# Logica_ADC.net
KiCad netlist of a schematic drawn in Altium Designer
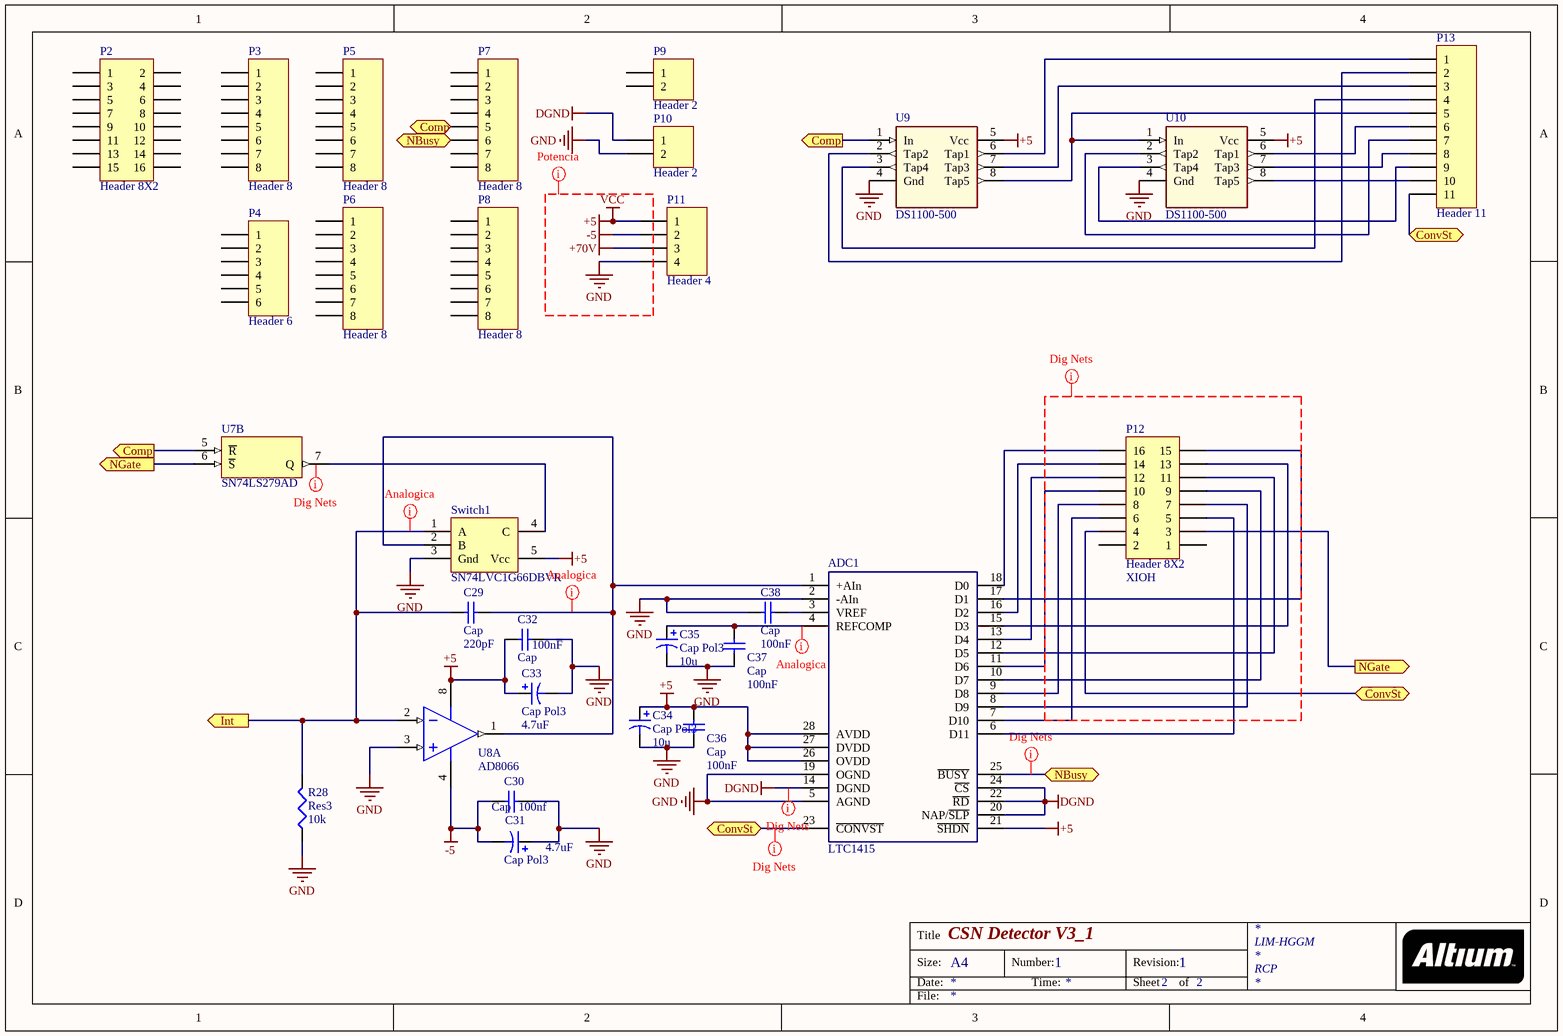
[diagram p0: Logica_ADC.SchDoc]

(export (version "E")
  (design (tool "Eeschema 10.0.6"))
  (components
    (comp (ref "ADC1")
      (value "LTC1415")
      (footprint "SO28_N")
      (libsource (lib "Integrated_Library1") (part "LTC1415"))
    )
    (comp (ref "C29")
      (value "Cap")
      (footprint "6-0805_N")
      (description "Capacitor")
      (fields (field (name "ALTIUM_VALUE") "220pF") (field (name "PUBLISHER") "Altium Limited"))
      (libsource (lib "Miscellaneous Devices") (part "Cap"))
    )
    (comp (ref "C30")
      (value "Cap")
      (footprint "6-0805_N")
      (description "Capacitor")
      (fields (field (name "ALTIUM_VALUE") "100nf") (field (name "PUBLISHER") "Altium Limited"))
      (libsource (lib "Miscellaneous Devices") (part "Cap"))
    )
    (comp (ref "C31")
      (value "Cap Pol3")
      (footprint "6-0805_N")
      (description "Polarized Capacitor (Surface Mount)")
      (fields (field (name "ALTIUM_VALUE") "4.7uF") (field (name "PUBLISHER") "Altium Limited"))
      (libsource (lib "Miscellaneous Devices") (part "Cap Pol3"))
    )
    (comp (ref "C32")
      (value "Cap")
      (footprint "6-0805_N")
      (description "Capacitor")
      (fields (field (name "ALTIUM_VALUE") "100nF") (field (name "PUBLISHER") "Altium Limited"))
      (libsource (lib "Miscellaneous Devices") (part "Cap"))
    )
    (comp (ref "C33")
      (value "Cap Pol3")
      (footprint "6-0805_N")
      (description "Polarized Capacitor (Surface Mount)")
      (fields (field (name "ALTIUM_VALUE") "4.7uF") (field (name "PUBLISHER") "Altium Limited"))
      (libsource (lib "Miscellaneous Devices") (part "Cap Pol3"))
    )
    (comp (ref "C34")
      (value "Cap Pol3")
      (footprint "6-0805_N")
      (description "Polarized Capacitor (Surface Mount)")
      (fields (field (name "ALTIUM_VALUE") "10u") (field (name "PUBLISHER") "Altium Limited"))
      (libsource (lib "Miscellaneous Devices") (part "Cap Pol3"))
    )
    (comp (ref "C35")
      (value "Cap Pol3")
      (footprint "6-0805_N")
      (description "Polarized Capacitor (Surface Mount)")
      (fields (field (name "ALTIUM_VALUE") "10u") (field (name "PUBLISHER") "Altium Limited"))
      (libsource (lib "Miscellaneous Devices") (part "Cap Pol3"))
    )
    (comp (ref "C36")
      (value "Cap")
      (footprint "6-0805_N")
      (description "Capacitor")
      (fields (field (name "ALTIUM_VALUE") "100nF") (field (name "PUBLISHER") "Altium Limited"))
      (libsource (lib "Miscellaneous Devices") (part "Cap"))
    )
    (comp (ref "C37")
      (value "Cap")
      (footprint "6-0805_N")
      (description "Capacitor")
      (fields (field (name "ALTIUM_VALUE") "100nF") (field (name "PUBLISHER") "Altium Limited"))
      (libsource (lib "Miscellaneous Devices") (part "Cap"))
    )
    (comp (ref "C38")
      (value "Cap")
      (footprint "6-0805_N")
      (description "Capacitor")
      (fields (field (name "ALTIUM_VALUE") "100nF") (field (name "PUBLISHER") "Altium Limited"))
      (libsource (lib "Miscellaneous Devices") (part "Cap"))
    )
    (comp (ref "P2")
      (value "Header 8X2")
      (footprint "HDR2X8")
      (description "Header, 8-Pin, Dual row")
      (fields (field (name "PUBLISHER") "Altium Limited"))
      (libsource (lib "Miscellaneous Connectors") (part "Header 8X2"))
    )
    (comp (ref "P3")
      (value "Header 8")
      (footprint "HDR1X8")
      (description "Header, 8-Pin")
      (fields (field (name "PUBLISHER") "Altium Limited"))
      (libsource (lib "Miscellaneous Connectors") (part "Header 8"))
    )
    (comp (ref "P4")
      (value "Header 6")
      (footprint "HDR1X6")
      (description "Header, 6-Pin")
      (fields (field (name "PUBLISHER") "Altium Limited"))
      (libsource (lib "Miscellaneous Connectors") (part "Header 6"))
    )
    (comp (ref "P5")
      (value "Header 8")
      (footprint "HDR1X8")
      (description "Header, 8-Pin")
      (fields (field (name "PUBLISHER") "Altium Limited"))
      (libsource (lib "Miscellaneous Connectors") (part "Header 8"))
    )
    (comp (ref "P6")
      (value "Header 8")
      (footprint "HDR1X8")
      (description "Header, 8-Pin")
      (fields (field (name "PUBLISHER") "Altium Limited"))
      (libsource (lib "Miscellaneous Connectors") (part "Header 8"))
    )
    (comp (ref "P7")
      (value "Header 8")
      (footprint "HDR1X8")
      (description "Header, 8-Pin")
      (fields (field (name "PUBLISHER") "Altium Limited"))
      (libsource (lib "Miscellaneous Connectors") (part "Header 8"))
    )
    (comp (ref "P8")
      (value "Header 8")
      (footprint "HDR1X8")
      (description "Header, 8-Pin")
      (fields (field (name "PUBLISHER") "Altium Limited"))
      (libsource (lib "Miscellaneous Connectors") (part "Header 8"))
    )
    (comp (ref "P9")
      (value "Header 2")
      (footprint "HDR1X2")
      (description "Header, 2-Pin")
      (fields (field (name "PUBLISHER") "Altium Limited"))
      (libsource (lib "Miscellaneous Connectors") (part "Header 2"))
    )
    (comp (ref "P10")
      (value "Header 2")
      (footprint "HDR1X2")
      (description "Header, 2-Pin")
      (fields (field (name "PUBLISHER") "Altium Limited"))
      (libsource (lib "Miscellaneous Connectors") (part "Header 2"))
    )
    (comp (ref "P11")
      (value "Header 4")
      (footprint "HDR1X4")
      (description "Header, 4-Pin")
      (fields (field (name "PUBLISHER") "Altium Limited"))
      (libsource (lib "Miscellaneous Connectors") (part "Header 4"))
    )
    (comp (ref "P12")
      (value "Header 8X2")
      (footprint "HDR2X8")
      (description "Header, 8-Pin, Dual row")
      (fields (field (name "CON_ARDUINO") "XIOH") (field (name "PUBLISHER") "Altium Limited"))
      (libsource (lib "") (part "Header 8X2_1"))
    )
    (comp (ref "P13")
      (value "Header 11")
      (footprint "HDR1X11")
      (description "Header, 11-Pin")
      (fields (field (name "PUBLISHER") "Altium Limited"))
      (libsource (lib "Miscellaneous Connectors") (part "Header 11"))
    )
    (comp (ref "R28")
      (value "Res3")
      (footprint "6-0805_N")
      (description "Resistor")
      (fields (field (name "ALTIUM_VALUE") "10k") (field (name "PUBLISHER") "Altium Limited"))
      (libsource (lib "Miscellaneous Devices") (part "Res3"))
    )
    (comp (ref "Switch1")
      (value "SN74LVC1G66DBVR")
      (footprint "SOT23-5_N")
      (libsource (lib "Integrated_Library1") (part "SN74LVC1G66DBVR"))
    )
    (comp (ref "U7")
      (value "SN74LS279AD")
      (footprint "D016_N")
      (description "Quadruple S-R Latches")
      (fields (field (name "PUBLISHER") "Altium Limited"))
      (libsource (lib "TI Logic Latch") (part "SN74LS279AD"))
    )
    (comp (ref "U8")
      (value "AD8066")
      (footprint "S8_N")
      (description "Low Cost Dual Video Amplifier")
      (fields (field (name "PUBLISHER") "Altium Limited"))
      (libsource (lib "LT Video Amplifier") (part "LT1253CS8"))
    )
    (comp (ref "U9")
      (value "DS1100-500")
      (footprint "SO-8_L")
      (libsource (lib "Schlib1") (part "DS1100-500"))
    )
    (comp (ref "U10")
      (value "DS1100-500")
      (footprint "SO-8_L")
      (libsource (lib "Schlib1") (part "DS1100-500"))
    )
  )
  (nets
    (net (code "1") (name "+5") (class "Default")
      (node (ref "ADC1") (pin "21") (pinfunction "~{SHDN}_21") (pintype "passive"))
      (node (ref "ADC1") (pin "26") (pinfunction "OVDD_26") (pintype "passive"))
      (node (ref "ADC1") (pin "27") (pinfunction "DVDD_27") (pintype "passive"))
      (node (ref "ADC1") (pin "28") (pinfunction "AVDD_28") (pintype "passive"))
      (node (ref "C32") (pin "2") (pinfunction "2_2") (pintype "passive"))
      (node (ref "C33") (pin "1") (pinfunction "1_1") (pintype "passive"))
      (node (ref "C34") (pin "1") (pinfunction "1_1") (pintype "passive"))
      (node (ref "C36") (pin "2") (pinfunction "2_2") (pintype "passive"))
      (node (ref "P11") (pin "1") (pinfunction "1_1") (pintype "passive"))
      (node (ref "Switch1") (pin "5") (pinfunction "Vcc_5") (pintype "passive"))
      (node (ref "U10") (pin "5") (pinfunction "Vcc_5") (pintype "power_in"))
      (node (ref "U7") (pin "16") (pinfunction "VCC_16") (pintype "power_in"))
      (node (ref "U8") (pin "8") (pinfunction "V+_8") (pintype "power_in"))
      (node (ref "U9") (pin "5") (pinfunction "Vcc_5") (pintype "power_in"))
    )
    (net (code "2") (name "+70V") (class "Default")
      (node (ref "P11") (pin "3") (pinfunction "3_3") (pintype "passive"))
    )
    (net (code "3") (name "-5") (class "Default")
      (node (ref "C30") (pin "1") (pinfunction "1_1") (pintype "passive"))
      (node (ref "C31") (pin "2") (pinfunction "2_2") (pintype "passive"))
      (node (ref "P11") (pin "2") (pinfunction "2_2") (pintype "passive"))
      (node (ref "U8") (pin "4") (pinfunction "V-_4") (pintype "power_in"))
    )
    (net (code "4") (name "/Comp") (class "Default")
      (node (ref "P7") (pin "5") (pinfunction "5_5") (pintype "passive"))
      (node (ref "U7") (pin "5") (pinfunction "~{R}_5") (pintype "input"))
      (node (ref "U9") (pin "1") (pinfunction "In_1") (pintype "input"))
    )
    (net (code "5") (name "/ConvSt") (class "Default")
      (node (ref "ADC1") (pin "23") (pinfunction "~{CONVST}_23") (pintype "passive"))
      (node (ref "P12") (pin "4") (pinfunction "4_4") (pintype "passive"))
      (node (ref "P13") (pin "11") (pinfunction "11_11") (pintype "passive"))
    )
    (net (code "6") (name "/Int") (class "Default")
      (node (ref "C29") (pin "1") (pinfunction "1_1") (pintype "passive"))
      (node (ref "R28") (pin "2") (pinfunction "2_2") (pintype "passive"))
      (node (ref "Switch1") (pin "1") (pinfunction "A_1") (pintype "passive"))
      (node (ref "U8") (pin "2") (pinfunction "IN-_2") (pintype "input"))
    )
    (net (code "7") (name "/NBusy") (class "Default")
      (node (ref "ADC1") (pin "25") (pinfunction "~{BUSY}_25") (pintype "passive"))
      (node (ref "P7") (pin "6") (pinfunction "6_6") (pintype "passive"))
    )
    (net (code "8") (name "/NGate") (class "Default")
      (node (ref "P12") (pin "3") (pinfunction "3_3") (pintype "passive"))
      (node (ref "U7") (pin "6") (pinfunction "~{S}_6") (pintype "input"))
    )
    (net (code "9") (name "DGND") (class "Default")
      (node (ref "ADC1") (pin "14") (pinfunction "DGND_14") (pintype "passive"))
      (node (ref "ADC1") (pin "20") (pinfunction "NAP/~{SLP}_20") (pintype "passive"))
      (node (ref "ADC1") (pin "22") (pinfunction "~{RD}_22") (pintype "passive"))
      (node (ref "ADC1") (pin "24") (pinfunction "~{CS}_24") (pintype "passive"))
      (node (ref "P10") (pin "1") (pinfunction "1_1") (pintype "passive"))
    )
    (net (code "10") (name "GND") (class "Default")
      (node (ref "ADC1") (pin "19") (pinfunction "OGND_19") (pintype "passive"))
      (node (ref "ADC1") (pin "2") (pinfunction "-AIn_2") (pintype "passive"))
      (node (ref "ADC1") (pin "5") (pinfunction "AGND_5") (pintype "passive"))
      (node (ref "C30") (pin "2") (pinfunction "2_2") (pintype "passive"))
      (node (ref "C31") (pin "1") (pinfunction "1_1") (pintype "passive"))
      (node (ref "C32") (pin "1") (pinfunction "1_1") (pintype "passive"))
      (node (ref "C33") (pin "2") (pinfunction "2_2") (pintype "passive"))
      (node (ref "C34") (pin "2") (pinfunction "2_2") (pintype "passive"))
      (node (ref "C35") (pin "2") (pinfunction "2_2") (pintype "passive"))
      (node (ref "C36") (pin "1") (pinfunction "1_1") (pintype "passive"))
      (node (ref "C37") (pin "1") (pinfunction "1_1") (pintype "passive"))
      (node (ref "C38") (pin "2") (pinfunction "2_2") (pintype "passive"))
      (node (ref "P10") (pin "2") (pinfunction "2_2") (pintype "passive"))
      (node (ref "P11") (pin "4") (pinfunction "4_4") (pintype "passive"))
      (node (ref "R28") (pin "1") (pinfunction "1_1") (pintype "passive"))
      (node (ref "Switch1") (pin "3") (pinfunction "Gnd_3") (pintype "passive"))
      (node (ref "U10") (pin "4") (pinfunction "Gnd_4") (pintype "power_in"))
      (node (ref "U7") (pin "8") (pinfunction "GND_8") (pintype "power_in"))
      (node (ref "U8") (pin "3") (pinfunction "IN+_3") (pintype "input"))
      (node (ref "U9") (pin "4") (pinfunction "Gnd_4") (pintype "power_in"))
    )
    (net (code "11") (name "Net-(ADC1-+AIn)") (class "Default")
      (node (ref "ADC1") (pin "1") (pinfunction "+AIn_1") (pintype "passive"))
      (node (ref "C29") (pin "2") (pinfunction "2_2") (pintype "passive"))
      (node (ref "Switch1") (pin "2") (pinfunction "B_2") (pintype "passive"))
      (node (ref "U8") (pin "1") (pinfunction "OUT_1") (pintype "output"))
    )
    (net (code "12") (name "Net-(ADC1-D0)") (class "Default")
      (node (ref "ADC1") (pin "18") (pinfunction "D0_18") (pintype "passive"))
      (node (ref "P12") (pin "16") (pinfunction "16_16") (pintype "passive"))
    )
    (net (code "13") (name "Net-(ADC1-D1)") (class "Default")
      (node (ref "ADC1") (pin "17") (pinfunction "D1_17") (pintype "passive"))
      (node (ref "P12") (pin "15") (pinfunction "15_15") (pintype "passive"))
    )
    (net (code "14") (name "Net-(ADC1-D2)") (class "Default")
      (node (ref "ADC1") (pin "16") (pinfunction "D2_16") (pintype "passive"))
      (node (ref "P12") (pin "14") (pinfunction "14_14") (pintype "passive"))
    )
    (net (code "15") (name "Net-(ADC1-D3)") (class "Default")
      (node (ref "ADC1") (pin "15") (pinfunction "D3_15") (pintype "passive"))
      (node (ref "P12") (pin "13") (pinfunction "13_13") (pintype "passive"))
    )
    (net (code "16") (name "Net-(ADC1-D4)") (class "Default")
      (node (ref "ADC1") (pin "13") (pinfunction "D4_13") (pintype "passive"))
      (node (ref "P12") (pin "12") (pinfunction "12_12") (pintype "passive"))
    )
    (net (code "17") (name "Net-(ADC1-D5)") (class "Default")
      (node (ref "ADC1") (pin "12") (pinfunction "D5_12") (pintype "passive"))
      (node (ref "P12") (pin "11") (pinfunction "11_11") (pintype "passive"))
    )
    (net (code "18") (name "Net-(ADC1-D6)") (class "Default")
      (node (ref "ADC1") (pin "11") (pinfunction "D6_11") (pintype "passive"))
      (node (ref "P12") (pin "10") (pinfunction "10_10") (pintype "passive"))
    )
    (net (code "19") (name "Net-(ADC1-D7)") (class "Default")
      (node (ref "ADC1") (pin "10") (pinfunction "D7_10") (pintype "passive"))
      (node (ref "P12") (pin "9") (pinfunction "9_9") (pintype "passive"))
    )
    (net (code "20") (name "Net-(ADC1-D8)") (class "Default")
      (node (ref "ADC1") (pin "9") (pinfunction "D8_9") (pintype "passive"))
      (node (ref "P12") (pin "8") (pinfunction "8_8") (pintype "passive"))
    )
    (net (code "21") (name "Net-(ADC1-D9)") (class "Default")
      (node (ref "ADC1") (pin "8") (pinfunction "D9_8") (pintype "passive"))
      (node (ref "P12") (pin "7") (pinfunction "7_7") (pintype "passive"))
    )
    (net (code "22") (name "Net-(ADC1-D10)") (class "Default")
      (node (ref "ADC1") (pin "7") (pinfunction "D10_7") (pintype "passive"))
      (node (ref "P12") (pin "6") (pinfunction "6_6") (pintype "passive"))
    )
    (net (code "23") (name "Net-(ADC1-D11)") (class "Default")
      (node (ref "ADC1") (pin "6") (pinfunction "D11_6") (pintype "passive"))
      (node (ref "P12") (pin "5") (pinfunction "5_5") (pintype "passive"))
    )
    (net (code "24") (name "Net-(ADC1-REFCOMP)") (class "Default")
      (node (ref "ADC1") (pin "4") (pinfunction "REFCOMP_4") (pintype "passive"))
      (node (ref "C35") (pin "1") (pinfunction "1_1") (pintype "passive"))
      (node (ref "C37") (pin "2") (pinfunction "2_2") (pintype "passive"))
    )
    (net (code "25") (name "Net-(ADC1-VREF)") (class "Default")
      (node (ref "ADC1") (pin "3") (pinfunction "VREF_3") (pintype "passive"))
      (node (ref "C38") (pin "1") (pinfunction "1_1") (pintype "passive"))
    )
    (net (code "26") (name "Net-(Switch1-C)") (class "Default")
      (node (ref "Switch1") (pin "4") (pinfunction "C_4") (pintype "passive"))
      (node (ref "U7") (pin "7") (pinfunction "Q_7") (pintype "output"))
    )
    (net (code "27") (name "Net-(U9-Tap1)") (class "Default")
      (node (ref "P13") (pin "1") (pinfunction "1_1") (pintype "passive"))
      (node (ref "U9") (pin "6") (pinfunction "Tap1_6") (pintype "output"))
    )
    (net (code "28") (name "Net-(U9-Tap2)") (class "Default")
      (node (ref "P13") (pin "2") (pinfunction "2_2") (pintype "passive"))
      (node (ref "U9") (pin "2") (pinfunction "Tap2_2") (pintype "output"))
    )
    (net (code "29") (name "Net-(U9-Tap3)") (class "Default")
      (node (ref "P13") (pin "3") (pinfunction "3_3") (pintype "passive"))
      (node (ref "U9") (pin "7") (pinfunction "Tap3_7") (pintype "output"))
    )
    (net (code "30") (name "Net-(U9-Tap4)") (class "Default")
      (node (ref "P13") (pin "4") (pinfunction "4_4") (pintype "passive"))
      (node (ref "U9") (pin "3") (pinfunction "Tap4_3") (pintype "output"))
    )
    (net (code "31") (name "Net-(U10-In)") (class "Default")
      (node (ref "P13") (pin "5") (pinfunction "5_5") (pintype "passive"))
      (node (ref "U10") (pin "1") (pinfunction "In_1") (pintype "input"))
      (node (ref "U9") (pin "8") (pinfunction "Tap5_8") (pintype "output"))
    )
    (net (code "32") (name "Net-(U10-Tap1)") (class "Default")
      (node (ref "P13") (pin "6") (pinfunction "6_6") (pintype "passive"))
      (node (ref "U10") (pin "6") (pinfunction "Tap1_6") (pintype "output"))
    )
    (net (code "33") (name "Net-(U10-Tap2)") (class "Default")
      (node (ref "P13") (pin "7") (pinfunction "7_7") (pintype "passive"))
      (node (ref "U10") (pin "2") (pinfunction "Tap2_2") (pintype "output"))
    )
    (net (code "34") (name "Net-(U10-Tap3)") (class "Default")
      (node (ref "P13") (pin "8") (pinfunction "8_8") (pintype "passive"))
      (node (ref "U10") (pin "7") (pinfunction "Tap3_7") (pintype "output"))
    )
    (net (code "35") (name "Net-(U10-Tap4)") (class "Default")
      (node (ref "P13") (pin "9") (pinfunction "9_9") (pintype "passive"))
      (node (ref "U10") (pin "3") (pinfunction "Tap4_3") (pintype "output"))
    )
    (net (code "36") (name "Net-(U10-Tap5)") (class "Default")
      (node (ref "P13") (pin "10") (pinfunction "10_10") (pintype "passive"))
      (node (ref "U10") (pin "8") (pinfunction "Tap5_8") (pintype "output"))
    )
    (net (code "37") (name "unconnected-(P2-Pad1)") (class "Default")
      (node (ref "P2") (pin "1") (pinfunction "1_1") (pintype "passive"))
    )
    (net (code "38") (name "unconnected-(P2-Pad2)") (class "Default")
      (node (ref "P2") (pin "2") (pinfunction "2_2") (pintype "passive"))
    )
    (net (code "39") (name "unconnected-(P2-Pad3)") (class "Default")
      (node (ref "P2") (pin "3") (pinfunction "3_3") (pintype "passive"))
    )
    (net (code "40") (name "unconnected-(P2-Pad4)") (class "Default")
      (node (ref "P2") (pin "4") (pinfunction "4_4") (pintype "passive"))
    )
    (net (code "41") (name "unconnected-(P2-Pad5)") (class "Default")
      (node (ref "P2") (pin "5") (pinfunction "5_5") (pintype "passive"))
    )
    (net (code "42") (name "unconnected-(P2-Pad6)") (class "Default")
      (node (ref "P2") (pin "6") (pinfunction "6_6") (pintype "passive"))
    )
    (net (code "43") (name "unconnected-(P2-Pad7)") (class "Default")
      (node (ref "P2") (pin "7") (pinfunction "7_7") (pintype "passive"))
    )
    (net (code "44") (name "unconnected-(P2-Pad8)") (class "Default")
      (node (ref "P2") (pin "8") (pinfunction "8_8") (pintype "passive"))
    )
    (net (code "45") (name "unconnected-(P2-Pad9)") (class "Default")
      (node (ref "P2") (pin "9") (pinfunction "9_9") (pintype "passive"))
    )
    (net (code "46") (name "unconnected-(P2-Pad10)") (class "Default")
      (node (ref "P2") (pin "10") (pinfunction "10_10") (pintype "passive"))
    )
    (net (code "47") (name "unconnected-(P2-Pad11)") (class "Default")
      (node (ref "P2") (pin "11") (pinfunction "11_11") (pintype "passive"))
    )
    (net (code "48") (name "unconnected-(P2-Pad12)") (class "Default")
      (node (ref "P2") (pin "12") (pinfunction "12_12") (pintype "passive"))
    )
    (net (code "49") (name "unconnected-(P2-Pad13)") (class "Default")
      (node (ref "P2") (pin "13") (pinfunction "13_13") (pintype "passive"))
    )
    (net (code "50") (name "unconnected-(P2-Pad14)") (class "Default")
      (node (ref "P2") (pin "14") (pinfunction "14_14") (pintype "passive"))
    )
    (net (code "51") (name "unconnected-(P2-Pad15)") (class "Default")
      (node (ref "P2") (pin "15") (pinfunction "15_15") (pintype "passive"))
    )
    (net (code "52") (name "unconnected-(P2-Pad16)") (class "Default")
      (node (ref "P2") (pin "16") (pinfunction "16_16") (pintype "passive"))
    )
    (net (code "53") (name "unconnected-(P3-Pad1)") (class "Default")
      (node (ref "P3") (pin "1") (pinfunction "1_1") (pintype "passive"))
    )
    (net (code "54") (name "unconnected-(P3-Pad2)") (class "Default")
      (node (ref "P3") (pin "2") (pinfunction "2_2") (pintype "passive"))
    )
    (net (code "55") (name "unconnected-(P3-Pad3)") (class "Default")
      (node (ref "P3") (pin "3") (pinfunction "3_3") (pintype "passive"))
    )
    (net (code "56") (name "unconnected-(P3-Pad4)") (class "Default")
      (node (ref "P3") (pin "4") (pinfunction "4_4") (pintype "passive"))
    )
    (net (code "57") (name "unconnected-(P3-Pad5)") (class "Default")
      (node (ref "P3") (pin "5") (pinfunction "5_5") (pintype "passive"))
    )
    (net (code "58") (name "unconnected-(P3-Pad6)") (class "Default")
      (node (ref "P3") (pin "6") (pinfunction "6_6") (pintype "passive"))
    )
    (net (code "59") (name "unconnected-(P3-Pad7)") (class "Default")
      (node (ref "P3") (pin "7") (pinfunction "7_7") (pintype "passive"))
    )
    (net (code "60") (name "unconnected-(P3-Pad8)") (class "Default")
      (node (ref "P3") (pin "8") (pinfunction "8_8") (pintype "passive"))
    )
    (net (code "61") (name "unconnected-(P4-Pad1)") (class "Default")
      (node (ref "P4") (pin "1") (pinfunction "1_1") (pintype "passive"))
    )
    (net (code "62") (name "unconnected-(P4-Pad2)") (class "Default")
      (node (ref "P4") (pin "2") (pinfunction "2_2") (pintype "passive"))
    )
    (net (code "63") (name "unconnected-(P4-Pad3)") (class "Default")
      (node (ref "P4") (pin "3") (pinfunction "3_3") (pintype "passive"))
    )
    (net (code "64") (name "unconnected-(P4-Pad4)") (class "Default")
      (node (ref "P4") (pin "4") (pinfunction "4_4") (pintype "passive"))
    )
    (net (code "65") (name "unconnected-(P4-Pad5)") (class "Default")
      (node (ref "P4") (pin "5") (pinfunction "5_5") (pintype "passive"))
    )
    (net (code "66") (name "unconnected-(P4-Pad6)") (class "Default")
      (node (ref "P4") (pin "6") (pinfunction "6_6") (pintype "passive"))
    )
    (net (code "67") (name "unconnected-(P5-Pad1)") (class "Default")
      (node (ref "P5") (pin "1") (pinfunction "1_1") (pintype "passive"))
    )
    (net (code "68") (name "unconnected-(P5-Pad2)") (class "Default")
      (node (ref "P5") (pin "2") (pinfunction "2_2") (pintype "passive"))
    )
    (net (code "69") (name "unconnected-(P5-Pad3)") (class "Default")
      (node (ref "P5") (pin "3") (pinfunction "3_3") (pintype "passive"))
    )
    (net (code "70") (name "unconnected-(P5-Pad4)") (class "Default")
      (node (ref "P5") (pin "4") (pinfunction "4_4") (pintype "passive"))
    )
    (net (code "71") (name "unconnected-(P5-Pad5)") (class "Default")
      (node (ref "P5") (pin "5") (pinfunction "5_5") (pintype "passive"))
    )
    (net (code "72") (name "unconnected-(P5-Pad6)") (class "Default")
      (node (ref "P5") (pin "6") (pinfunction "6_6") (pintype "passive"))
    )
    (net (code "73") (name "unconnected-(P5-Pad7)") (class "Default")
      (node (ref "P5") (pin "7") (pinfunction "7_7") (pintype "passive"))
    )
    (net (code "74") (name "unconnected-(P5-Pad8)") (class "Default")
      (node (ref "P5") (pin "8") (pinfunction "8_8") (pintype "passive"))
    )
    (net (code "75") (name "unconnected-(P6-Pad1)") (class "Default")
      (node (ref "P6") (pin "1") (pinfunction "1_1") (pintype "passive"))
    )
    (net (code "76") (name "unconnected-(P6-Pad2)") (class "Default")
      (node (ref "P6") (pin "2") (pinfunction "2_2") (pintype "passive"))
    )
    (net (code "77") (name "unconnected-(P6-Pad3)") (class "Default")
      (node (ref "P6") (pin "3") (pinfunction "3_3") (pintype "passive"))
    )
    (net (code "78") (name "unconnected-(P6-Pad4)") (class "Default")
      (node (ref "P6") (pin "4") (pinfunction "4_4") (pintype "passive"))
    )
    (net (code "79") (name "unconnected-(P6-Pad5)") (class "Default")
      (node (ref "P6") (pin "5") (pinfunction "5_5") (pintype "passive"))
    )
    (net (code "80") (name "unconnected-(P6-Pad6)") (class "Default")
      (node (ref "P6") (pin "6") (pinfunction "6_6") (pintype "passive"))
    )
    (net (code "81") (name "unconnected-(P6-Pad7)") (class "Default")
      (node (ref "P6") (pin "7") (pinfunction "7_7") (pintype "passive"))
    )
    (net (code "82") (name "unconnected-(P6-Pad8)") (class "Default")
      (node (ref "P6") (pin "8") (pinfunction "8_8") (pintype "passive"))
    )
    (net (code "83") (name "unconnected-(P7-Pad1)") (class "Default")
      (node (ref "P7") (pin "1") (pinfunction "1_1") (pintype "passive"))
    )
    (net (code "84") (name "unconnected-(P7-Pad2)") (class "Default")
      (node (ref "P7") (pin "2") (pinfunction "2_2") (pintype "passive"))
    )
    (net (code "85") (name "unconnected-(P7-Pad3)") (class "Default")
      (node (ref "P7") (pin "3") (pinfunction "3_3") (pintype "passive"))
    )
    (net (code "86") (name "unconnected-(P7-Pad4)") (class "Default")
      (node (ref "P7") (pin "4") (pinfunction "4_4") (pintype "passive"))
    )
    (net (code "87") (name "unconnected-(P7-Pad7)") (class "Default")
      (node (ref "P7") (pin "7") (pinfunction "7_7") (pintype "passive"))
    )
    (net (code "88") (name "unconnected-(P7-Pad8)") (class "Default")
      (node (ref "P7") (pin "8") (pinfunction "8_8") (pintype "passive"))
    )
    (net (code "89") (name "unconnected-(P8-Pad1)") (class "Default")
      (node (ref "P8") (pin "1") (pinfunction "1_1") (pintype "passive"))
    )
    (net (code "90") (name "unconnected-(P8-Pad2)") (class "Default")
      (node (ref "P8") (pin "2") (pinfunction "2_2") (pintype "passive"))
    )
    (net (code "91") (name "unconnected-(P8-Pad3)") (class "Default")
      (node (ref "P8") (pin "3") (pinfunction "3_3") (pintype "passive"))
    )
    (net (code "92") (name "unconnected-(P8-Pad4)") (class "Default")
      (node (ref "P8") (pin "4") (pinfunction "4_4") (pintype "passive"))
    )
    (net (code "93") (name "unconnected-(P8-Pad5)") (class "Default")
      (node (ref "P8") (pin "5") (pinfunction "5_5") (pintype "passive"))
    )
    (net (code "94") (name "unconnected-(P8-Pad6)") (class "Default")
      (node (ref "P8") (pin "6") (pinfunction "6_6") (pintype "passive"))
    )
    (net (code "95") (name "unconnected-(P8-Pad7)") (class "Default")
      (node (ref "P8") (pin "7") (pinfunction "7_7") (pintype "passive"))
    )
    (net (code "96") (name "unconnected-(P8-Pad8)") (class "Default")
      (node (ref "P8") (pin "8") (pinfunction "8_8") (pintype "passive"))
    )
    (net (code "97") (name "unconnected-(P9-Pad1)") (class "Default")
      (node (ref "P9") (pin "1") (pinfunction "1_1") (pintype "passive"))
    )
    (net (code "98") (name "unconnected-(P9-Pad2)") (class "Default")
      (node (ref "P9") (pin "2") (pinfunction "2_2") (pintype "passive"))
    )
    (net (code "99") (name "unconnected-(P12-Pad1)") (class "Default")
      (node (ref "P12") (pin "1") (pinfunction "1_1") (pintype "passive"))
    )
    (net (code "100") (name "unconnected-(P12-Pad2)") (class "Default")
      (node (ref "P12") (pin "2") (pinfunction "2_2") (pintype "passive"))
    )
  )
)
